# 1301_10A_01_400_1.net
KiCad netlist of a schematic drawn in Altium Designer
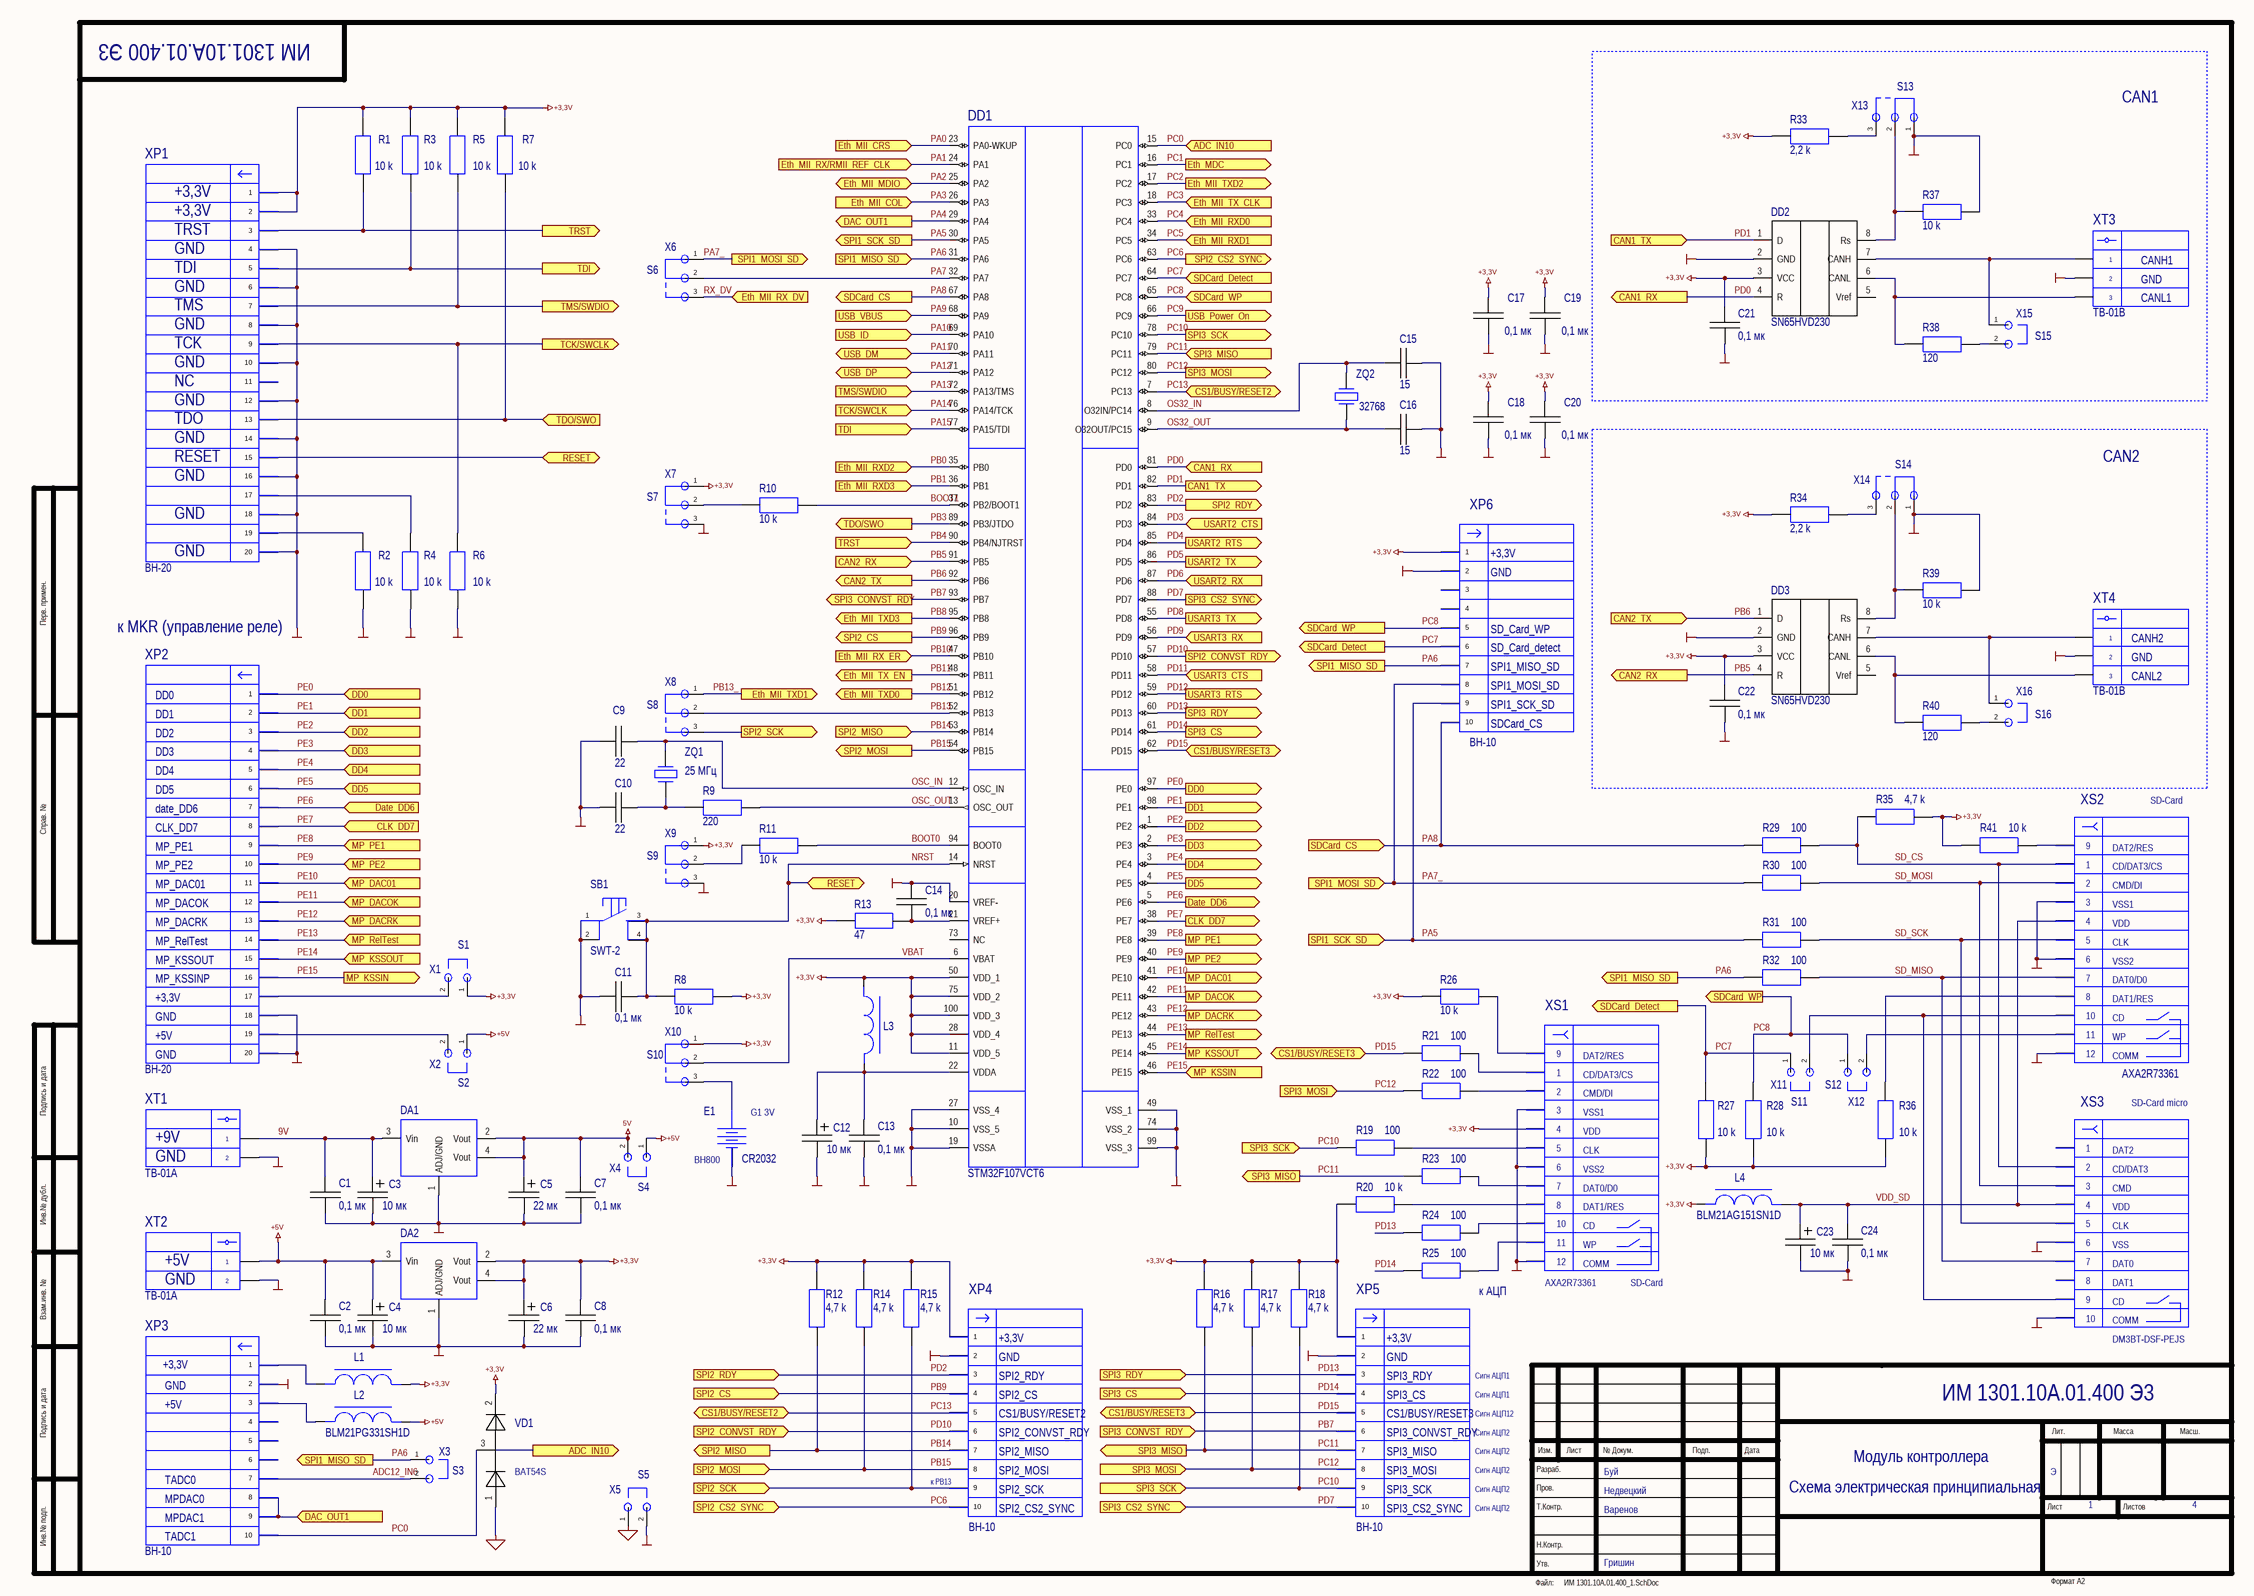
[diagram p0: ИМ 1301.10A.01.400_1.SchDoc]

(export (version "E")
  (design (tool "Eeschema 10.0.6"))
  (components
    (comp (ref "C1")
      (value "0,1 мк")
      (footprint "CAPC_1206")
      (description "Capasitor")
      (fields (field (name "PART NUMBER") "C"))
      (libsource (lib "RLC_GOST") (part "C"))
    )
    (comp (ref "C2")
      (value "0,1 мк")
      (footprint "CAPC_1206")
      (description "Capasitor")
      (fields (field (name "PART NUMBER") "C"))
      (libsource (lib "RLC_GOST") (part "C"))
    )
    (comp (ref "C3")
      (value "10 мк")
      (footprint "3216")
      (description "Capasitor_polar")
      (fields (field (name "PART NUMBER") "CapPol"))
      (libsource (lib "RLC_GOST") (part "CapPol"))
    )
    (comp (ref "C4")
      (value "10 мк")
      (footprint "3216")
      (description "Capasitor_polar")
      (fields (field (name "PART NUMBER") "CapPol"))
      (libsource (lib "RLC_GOST") (part "CapPol"))
    )
    (comp (ref "C5")
      (value "22 мк")
      (footprint "3216")
      (description "Capasitor_polar")
      (fields (field (name "PART NUMBER") "CapPol"))
      (libsource (lib "RLC_GOST") (part "CapPol"))
    )
    (comp (ref "C6")
      (value "22 мк")
      (footprint "3216")
      (description "Capasitor_polar")
      (fields (field (name "PART NUMBER") "CapPol"))
      (libsource (lib "RLC_GOST") (part "CapPol"))
    )
    (comp (ref "C7")
      (value "0,1 мк")
      (footprint "CAPC_1206")
      (description "Capasitor")
      (fields (field (name "PART NUMBER") "C"))
      (libsource (lib "RLC_GOST") (part "C"))
    )
    (comp (ref "C8")
      (value "0,1 мк")
      (footprint "CAPC_1206")
      (description "Capasitor")
      (fields (field (name "PART NUMBER") "C"))
      (libsource (lib "RLC_GOST") (part "C"))
    )
    (comp (ref "C9")
      (value "22")
      (footprint "CAPC_1206")
      (description "Capasitor")
      (libsource (lib "RLC_GOST") (part "C"))
    )
    (comp (ref "C10")
      (value "22")
      (footprint "CAPC_1206")
      (description "Capasitor")
      (libsource (lib "RLC_GOST") (part "C"))
    )
    (comp (ref "C11")
      (value "0,1 мк")
      (footprint "CAPC_1206")
      (description "Capasitor")
      (libsource (lib "RLC_GOST") (part "C"))
    )
    (comp (ref "C12")
      (value "10 мк")
      (footprint "3216")
      (description "Capasitor_polar")
      (fields (field (name "PART NUMBER") "CapPol"))
      (libsource (lib "RLC_GOST") (part "CapPol"))
    )
    (comp (ref "C13")
      (value "0,1 мк")
      (footprint "CAPC_1206")
      (description "Capasitor")
      (fields (field (name "PART NUMBER") "C"))
      (libsource (lib "RLC_GOST") (part "C"))
    )
    (comp (ref "C14")
      (value "0,1 мк")
      (footprint "CAPC_1206")
      (description "Capasitor")
      (fields (field (name "PART NUMBER") "C"))
      (libsource (lib "RLC_GOST") (part "C"))
    )
    (comp (ref "C15")
      (value "15")
      (footprint "CAPC_1206")
      (description "Capasitor")
      (libsource (lib "RLC_GOST") (part "C"))
    )
    (comp (ref "C16")
      (value "15")
      (footprint "CAPC_1206")
      (description "Capasitor")
      (libsource (lib "RLC_GOST") (part "C"))
    )
    (comp (ref "C17")
      (value "0,1 мк")
      (footprint "CAPC_1206")
      (description "Capasitor")
      (fields (field (name "PART NUMBER") "C"))
      (libsource (lib "RLC_GOST") (part "C"))
    )
    (comp (ref "C18")
      (value "0,1 мк")
      (footprint "CAPC_1206")
      (description "Capasitor")
      (fields (field (name "PART NUMBER") "C"))
      (libsource (lib "RLC_GOST") (part "C"))
    )
    (comp (ref "C19")
      (value "0,1 мк")
      (footprint "CAPC_1206")
      (description "Capasitor")
      (fields (field (name "PART NUMBER") "C"))
      (libsource (lib "RLC_GOST") (part "C"))
    )
    (comp (ref "C20")
      (value "0,1 мк")
      (footprint "CAPC_1206")
      (description "Capasitor")
      (fields (field (name "PART NUMBER") "C"))
      (libsource (lib "RLC_GOST") (part "C"))
    )
    (comp (ref "C21")
      (value "0,1 мк")
      (footprint "CAPC_1206")
      (description "Capasitor")
      (fields (field (name "PART NUMBER") "C"))
      (libsource (lib "RLC_GOST") (part "C"))
    )
    (comp (ref "C22")
      (value "0,1 мк")
      (footprint "CAPC_1206")
      (description "Capasitor")
      (fields (field (name "PART NUMBER") "C"))
      (libsource (lib "RLC_GOST") (part "C"))
    )
    (comp (ref "C23")
      (value "10 мк")
      (footprint "3216")
      (description "Capasitor_polar")
      (fields (field (name "PART NUMBER") "CapPol"))
      (libsource (lib "RLC_GOST") (part "CapPol"))
    )
    (comp (ref "C24")
      (value "0,1 мк")
      (footprint "CAPC_1206")
      (description "Capasitor")
      (fields (field (name "PART NUMBER") "C"))
      (libsource (lib "RLC_GOST") (part "C"))
    )
    (comp (ref "DA1")
      (value "LM1117")
      (footprint "SOT223")
      (description "Positive voltage regulators")
      (fields (field (name "MANUFACTURER") "National Semiconductor"))
      (libsource (lib "Stabil") (part "LM1117"))
    )
    (comp (ref "DA2")
      (value "LM1117")
      (footprint "SOT223")
      (description "Positive voltage regulators")
      (fields (field (name "MANUFACTURER") "National Semiconductor"))
      (libsource (lib "Stabil") (part "LM1117"))
    )
    (comp (ref "DD1")
      (value "STM32F107VCT6")
      (footprint "LQFP100")
      (description "STM32 ARM-based 32-bit MCU with 256 Kbytes Flash, 100-pin LQFP, Industrial Temperature")
      (fields (field (name "PUBLISHER") "Altium Limited"))
      (libsource (lib "STM32") (part "STM32F107VCT6"))
    )
    (comp (ref "DD2")
      (value "SN65HVD230")
      (footprint "SO8")
      (description "CAN transceivers")
      (libsource (lib "CAN") (part "SN65HVD230"))
    )
    (comp (ref "DD3")
      (value "SN65HVD230")
      (footprint "SO8")
      (description "CAN transceivers")
      (libsource (lib "CAN") (part "SN65HVD230"))
    )
    (comp (ref "E1")
      (value "BH800")
      (footprint "BATTERY_20mm")
      (fields (field (name "ALTIUM_VALUE") "CR2032") (field (name "G") "G1 3V"))
      (libsource (lib "Connectors") (part "BH800"))
    )
    (comp (ref "L1")
      (value "BLM21PG331SH1D")
      (footprint "C0805")
      (description "Ferrite bead")
      (libsource (lib "RLC_GOST") (part "B"))
    )
    (comp (ref "L2")
      (value "BLM21PG331SH1D")
      (footprint "C0805")
      (description "Ferrite bead")
      (libsource (lib "RLC_GOST") (part "B"))
    )
    (comp (ref "L3")
      (value "BLM21AG151SN1D")
      (footprint "C0805")
      (description "Ferrite bead")
      (libsource (lib "RLC_GOST") (part "B"))
    )
    (comp (ref "L4")
      (value "BLM21AG151SN1D")
      (footprint "C0805")
      (description "Ferrite bead")
      (libsource (lib "RLC_GOST") (part "B"))
    )
    (comp (ref "R1")
      (value "10 k")
      (footprint "SMD_1206")
      (description "Resistor,2 Pin")
      (libsource (lib "RLC_GOST") (part "R_Gost"))
    )
    (comp (ref "R2")
      (value "10 k")
      (footprint "SMD_1206")
      (description "Resistor,2 Pin")
      (libsource (lib "RLC_GOST") (part "R_Gost"))
    )
    (comp (ref "R3")
      (value "10 k")
      (footprint "SMD_1206")
      (description "Resistor,2 Pin")
      (libsource (lib "RLC_GOST") (part "R_Gost"))
    )
    (comp (ref "R4")
      (value "10 k")
      (footprint "SMD_1206")
      (description "Resistor,2 Pin")
      (libsource (lib "RLC_GOST") (part "R_Gost"))
    )
    (comp (ref "R5")
      (value "10 k")
      (footprint "SMD_1206")
      (description "Resistor,2 Pin")
      (libsource (lib "RLC_GOST") (part "R_Gost"))
    )
    (comp (ref "R6")
      (value "10 k")
      (footprint "SMD_1206")
      (description "Resistor,2 Pin")
      (libsource (lib "RLC_GOST") (part "R_Gost"))
    )
    (comp (ref "R7")
      (value "10 k")
      (footprint "SMD_1206")
      (description "Resistor,2 Pin")
      (libsource (lib "RLC_GOST") (part "R_Gost"))
    )
    (comp (ref "R8")
      (value "10 k")
      (footprint "SMD_1206")
      (description "Resistor,2 Pin")
      (libsource (lib "RLC_GOST") (part "R_Gost"))
    )
    (comp (ref "R9")
      (value "220")
      (footprint "SMD_1206")
      (description "Resistor,2 Pin")
      (libsource (lib "RLC_GOST") (part "R_Gost"))
    )
    (comp (ref "R10")
      (value "10 k")
      (footprint "SMD_1206")
      (description "Resistor,2 Pin")
      (libsource (lib "RLC_GOST") (part "R_Gost"))
    )
    (comp (ref "R11")
      (value "10 k")
      (footprint "SMD_1206")
      (description "Resistor,2 Pin")
      (libsource (lib "RLC_GOST") (part "R_Gost"))
    )
    (comp (ref "R12")
      (value "4,7 k")
      (footprint "SMD_1206")
      (description "Resistor,2 Pin")
      (libsource (lib "RLC_GOST") (part "R_Gost"))
    )
    (comp (ref "R13")
      (value "47")
      (footprint "SMD_1206")
      (description "Resistor,2 Pin")
      (libsource (lib "RLC_GOST") (part "R_Gost"))
    )
    (comp (ref "R14")
      (value "4,7 k")
      (footprint "SMD_1206")
      (description "Resistor,2 Pin")
      (libsource (lib "RLC_GOST") (part "R_Gost"))
    )
    (comp (ref "R15")
      (value "4,7 k")
      (footprint "SMD_1206")
      (description "Resistor,2 Pin")
      (libsource (lib "RLC_GOST") (part "R_Gost"))
    )
    (comp (ref "R16")
      (value "4,7 k")
      (footprint "SMD_1206")
      (description "Resistor,2 Pin")
      (libsource (lib "RLC_GOST") (part "R_Gost"))
    )
    (comp (ref "R17")
      (value "4,7 k")
      (footprint "SMD_1206")
      (description "Resistor,2 Pin")
      (libsource (lib "RLC_GOST") (part "R_Gost"))
    )
    (comp (ref "R18")
      (value "4,7 k")
      (footprint "SMD_1206")
      (description "Resistor,2 Pin")
      (libsource (lib "RLC_GOST") (part "R_Gost"))
    )
    (comp (ref "R19")
      (value "100")
      (footprint "SMD_1206")
      (description "Resistor,2 Pin")
      (libsource (lib "RLC_GOST") (part "R_Gost"))
    )
    (comp (ref "R20")
      (value "10 k")
      (footprint "SMD_1206")
      (description "Resistor,2 Pin")
      (libsource (lib "RLC_GOST") (part "R_Gost"))
    )
    (comp (ref "R21")
      (value "100")
      (footprint "SMD_1206")
      (description "Resistor,2 Pin")
      (libsource (lib "RLC_GOST") (part "R_Gost"))
    )
    (comp (ref "R22")
      (value "100")
      (footprint "SMD_1206")
      (description "Resistor,2 Pin")
      (libsource (lib "RLC_GOST") (part "R_Gost"))
    )
    (comp (ref "R23")
      (value "100")
      (footprint "SMD_1206")
      (description "Resistor,2 Pin")
      (libsource (lib "RLC_GOST") (part "R_Gost"))
    )
    (comp (ref "R24")
      (value "100")
      (footprint "SMD_1206")
      (description "Resistor,2 Pin")
      (libsource (lib "RLC_GOST") (part "R_Gost"))
    )
    (comp (ref "R25")
      (value "100")
      (footprint "SMD_1206")
      (description "Resistor,2 Pin")
      (libsource (lib "RLC_GOST") (part "R_Gost"))
    )
    (comp (ref "R26")
      (value "10 k")
      (footprint "SMD_1206")
      (description "Resistor,2 Pin")
      (libsource (lib "RLC_GOST") (part "R_Gost"))
    )
    (comp (ref "R27")
      (value "10 k")
      (footprint "SMD_1206")
      (description "Resistor,2 Pin")
      (libsource (lib "RLC_GOST") (part "R_Gost"))
    )
    (comp (ref "R28")
      (value "10 k")
      (footprint "SMD_1206")
      (description "Resistor,2 Pin")
      (libsource (lib "RLC_GOST") (part "R_Gost"))
    )
    (comp (ref "R29")
      (value "100")
      (footprint "SMD_1206")
      (description "Resistor,2 Pin")
      (libsource (lib "RLC_GOST") (part "R_Gost"))
    )
    (comp (ref "R30")
      (value "100")
      (footprint "SMD_1206")
      (description "Resistor,2 Pin")
      (libsource (lib "RLC_GOST") (part "R_Gost"))
    )
    (comp (ref "R31")
      (value "100")
      (footprint "SMD_1206")
      (description "Resistor,2 Pin")
      (libsource (lib "RLC_GOST") (part "R_Gost"))
    )
    (comp (ref "R32")
      (value "100")
      (footprint "SMD_1206")
      (description "Resistor,2 Pin")
      (libsource (lib "RLC_GOST") (part "R_Gost"))
    )
    (comp (ref "R33")
      (value "2,2 k")
      (footprint "SMD_1206")
      (description "Resistor,2 Pin")
      (libsource (lib "RLC_GOST") (part "R_Gost"))
    )
    (comp (ref "R34")
      (value "2,2 k")
      (footprint "SMD_1206")
      (description "Resistor,2 Pin")
      (libsource (lib "RLC_GOST") (part "R_Gost"))
    )
    (comp (ref "R35")
      (value "4,7 k")
      (footprint "SMD_1206")
      (description "Resistor,2 Pin")
      (libsource (lib "RLC_GOST") (part "R_Gost"))
    )
    (comp (ref "R36")
      (value "10 k")
      (footprint "SMD_1206")
      (description "Resistor,2 Pin")
      (libsource (lib "RLC_GOST") (part "R_Gost"))
    )
    (comp (ref "R37")
      (value "10 k")
      (footprint "SMD_1206")
      (description "Resistor,2 Pin")
      (libsource (lib "RLC_GOST") (part "R_Gost"))
    )
    (comp (ref "R38")
      (value "120")
      (footprint "SMD_1206")
      (description "Resistor,2 Pin")
      (libsource (lib "RLC_GOST") (part "R_Gost"))
    )
    (comp (ref "R39")
      (value "10 k")
      (footprint "SMD_1206")
      (description "Resistor,2 Pin")
      (libsource (lib "RLC_GOST") (part "R_Gost"))
    )
    (comp (ref "R40")
      (value "120")
      (footprint "SMD_1206")
      (description "Resistor,2 Pin")
      (libsource (lib "RLC_GOST") (part "R_Gost"))
    )
    (comp (ref "R41")
      (value "10 k")
      (footprint "SMD_1206")
      (description "Resistor,2 Pin")
      (libsource (lib "RLC_GOST") (part "R_Gost"))
    )
    (comp (ref "SB1")
      (value "SWT-2")
      (footprint "SWT2")
      (description "SWT-2, key")
      (libsource (lib "Keys") (part "SWT-2"))
    )
    (comp (ref "VD1")
      (value "BAT54S")
      (footprint "SOT23")
      (description "Diod Schottky, 3 pin")
      (fields (field (name "MANUFACTURER") "Fairchild"))
      (libsource (lib "Diod") (part "BS40-04"))
    )
    (comp (ref "X1")
      (value "PLS-02")
      (footprint "PLS-2")
      (fields (field (name "JAMPER") "S1"))
      (libsource (lib "Connectors") (part "J2"))
    )
    (comp (ref "X2")
      (value "PLS-02")
      (footprint "PLS-2")
      (fields (field (name "JAMPER") "S2"))
      (libsource (lib "Connectors") (part "J2"))
    )
    (comp (ref "X3")
      (value "PLS-02")
      (footprint "PLS-2")
      (fields (field (name "JAMPER") "S3"))
      (libsource (lib "Connectors") (part "J2"))
    )
    (comp (ref "X4")
      (value "PLS-02")
      (footprint "PLS-2")
      (fields (field (name "JAMPER") "S4"))
      (libsource (lib "Connectors") (part "J2"))
    )
    (comp (ref "X5")
      (value "PLS-02")
      (footprint "PLS-2")
      (fields (field (name "JAMPER") "S5"))
      (libsource (lib "Connectors") (part "J2"))
    )
    (comp (ref "X6")
      (value "PLS-03")
      (footprint "PLS-3")
      (fields (field (name "JAMPER") "S6"))
      (libsource (lib "Connectors") (part "J3"))
    )
    (comp (ref "X7")
      (value "PLS-03")
      (footprint "PLS-3")
      (fields (field (name "JAMPER") "S7"))
      (libsource (lib "Connectors") (part "J3"))
    )
    (comp (ref "X8")
      (value "PLS-03")
      (footprint "PLS-3")
      (fields (field (name "JAMPER") "S8"))
      (libsource (lib "Connectors") (part "J3"))
    )
    (comp (ref "X9")
      (value "PLS-03")
      (footprint "PLS-3")
      (fields (field (name "JAMPER") "S9"))
      (libsource (lib "Connectors") (part "J3"))
    )
    (comp (ref "X10")
      (value "PLS-03")
      (footprint "PLS-3")
      (fields (field (name "JAMPER") "S10"))
      (libsource (lib "Connectors") (part "J3"))
    )
    (comp (ref "X11")
      (value "PLS-02")
      (footprint "PLS-2")
      (fields (field (name "JAMPER") "S11"))
      (libsource (lib "Connectors") (part "J2"))
    )
    (comp (ref "X12")
      (value "PLS-02")
      (footprint "PLS-2")
      (fields (field (name "JAMPER") "S12"))
      (libsource (lib "Connectors") (part "J2"))
    )
    (comp (ref "X13")
      (value "PLS-03")
      (footprint "PLS-3")
      (fields (field (name "JAMPER") "S13"))
      (libsource (lib "Connectors") (part "J3"))
    )
    (comp (ref "X14")
      (value "PLS-03")
      (footprint "PLS-3")
      (fields (field (name "JAMPER") "S14"))
      (libsource (lib "Connectors") (part "J3"))
    )
    (comp (ref "X15")
      (value "PLS-02")
      (footprint "PLS-2")
      (fields (field (name "JAMPER") "S15"))
      (libsource (lib "Connectors") (part "J2"))
    )
    (comp (ref "X16")
      (value "PLS-02")
      (footprint "PLS-2")
      (fields (field (name "JAMPER") "S16"))
      (libsource (lib "Connectors") (part "J2"))
    )
    (comp (ref "XP1") (value "BH-20") (footprint "PLD-20") (libsource (lib "Connectors") (part "BH-20")))
    (comp (ref "XP2") (value "BH-20") (footprint "PLD-20") (libsource (lib "Connectors") (part "BH-20")))
    (comp (ref "XP3") (value "BH-10") (footprint "PLD-10") (libsource (lib "Connectors") (part "BH-10")))
    (comp (ref "XP4") (value "BH-10") (footprint "PLD-10") (libsource (lib "Connectors") (part "BH-10")))
    (comp (ref "XP5") (value "BH-10") (footprint "PLD-10") (libsource (lib "Connectors") (part "BH-10")))
    (comp (ref "XP6") (value "BH-10") (footprint "PLD-10") (libsource (lib "Connectors") (part "BH-10")))
    (comp (ref "XS1")
      (value "AXA2R73361")
      (footprint "SD_AXA2R")
      (description "SD-card socket")
      (fields (field (name "FUNCTION") "SD-Card"))
      (libsource (lib "Connectors") (part "SDcard"))
    )
    (comp (ref "XS2")
      (value "AXA2R73361")
      (footprint "SD_AXA2R")
      (description "SD-card socket")
      (fields (field (name "FUNCTION") "SD-Card"))
      (libsource (lib "Connectors") (part "SDcard"))
    )
    (comp (ref "XS3")
      (value "DM3BT-DSF-PEJS")
      (footprint "DM3BT-DSF-PEJS")
      (description "SD-card socket")
      (fields (field (name "FUNCTION") "SD-Card micro"))
      (libsource (lib "Connectors") (part "MicroSD"))
    )
    (comp (ref "XT1") (value "TB-01A") (footprint "TB-01A") (libsource (lib "Connectors") (part "TB-01A")))
    (comp (ref "XT2") (value "TB-01A") (footprint "TB-01A") (libsource (lib "Connectors") (part "TB-01A")))
    (comp (ref "XT3") (value "TB-01B") (footprint "TB-01B") (libsource (lib "Connectors") (part "TB-01B")))
    (comp (ref "XT4") (value "TB-01B") (footprint "TB-01B") (libsource (lib "Connectors") (part "TB-01B")))
    (comp (ref "ZQ1")
      (value "25 МГц")
      (footprint "HC-49U_5mm")
      (description "OSC")
      (libsource (lib "Resonators") (part "OSC"))
    )
    (comp (ref "ZQ2")
      (value "32768")
      (footprint "DT-38P")
      (description "OSC")
      (libsource (lib "Resonators") (part "OSC"))
    )
  )
  (nets
    (net (code "1") (name "+3,3V") (class "Default")
      (node (ref "C17") (pin "1") (pinfunction "1_1") (pintype "passive"))
      (node (ref "C18") (pin "1") (pinfunction "1_1") (pintype "passive"))
      (node (ref "C19") (pin "1") (pinfunction "1_1") (pintype "passive"))
      (node (ref "C20") (pin "1") (pinfunction "1_1") (pintype "passive"))
      (node (ref "C21") (pin "1") (pinfunction "1_1") (pintype "passive"))
      (node (ref "C22") (pin "1") (pinfunction "1_1") (pintype "passive"))
      (node (ref "C6") (pin "1") (pinfunction "+_1") (pintype "passive"))
      (node (ref "C8") (pin "1") (pinfunction "1_1") (pintype "passive"))
      (node (ref "DA2") (pin "2") (pinfunction "Vout_2") (pintype "power_in"))
      (node (ref "DA2") (pin "4") (pinfunction "Vout_4") (pintype "passive"))
      (node (ref "DD1") (pin "100") (pinfunction "VDD_3_100") (pintype "power_in"))
      (node (ref "DD1") (pin "11") (pinfunction "VDD_5_11") (pintype "power_in"))
      (node (ref "DD1") (pin "28") (pinfunction "VDD_4_28") (pintype "power_in"))
      (node (ref "DD1") (pin "50") (pinfunction "VDD_1_50") (pintype "power_in"))
      (node (ref "DD1") (pin "75") (pinfunction "VDD_2_75") (pintype "power_in"))
      (node (ref "DD2") (pin "3") (pinfunction "VCC_3") (pintype "power_in"))
      (node (ref "DD3") (pin "3") (pinfunction "VCC_3") (pintype "power_in"))
      (node (ref "L1") (pin "2") (pinfunction "2_2") (pintype "passive"))
      (node (ref "L3") (pin "1") (pinfunction "1_1") (pintype "passive"))
      (node (ref "L4") (pin "1") (pinfunction "1_1") (pintype "passive"))
      (node (ref "R1") (pin "2") (pinfunction "2_2") (pintype "passive"))
      (node (ref "R12") (pin "2") (pinfunction "2_2") (pintype "passive"))
      (node (ref "R13") (pin "2") (pinfunction "2_2") (pintype "passive"))
      (node (ref "R14") (pin "2") (pinfunction "2_2") (pintype "passive"))
      (node (ref "R15") (pin "2") (pinfunction "2_2") (pintype "passive"))
      (node (ref "R16") (pin "2") (pinfunction "2_2") (pintype "passive"))
      (node (ref "R17") (pin "2") (pinfunction "2_2") (pintype "passive"))
      (node (ref "R18") (pin "2") (pinfunction "2_2") (pintype "passive"))
      (node (ref "R20") (pin "2") (pinfunction "2_2") (pintype "passive"))
      (node (ref "R26") (pin "1") (pinfunction "1_1") (pintype "passive"))
      (node (ref "R27") (pin "2") (pinfunction "2_2") (pintype "passive"))
      (node (ref "R28") (pin "2") (pinfunction "2_2") (pintype "passive"))
      (node (ref "R3") (pin "2") (pinfunction "2_2") (pintype "passive"))
      (node (ref "R33") (pin "1") (pinfunction "1_1") (pintype "passive"))
      (node (ref "R34") (pin "1") (pinfunction "1_1") (pintype "passive"))
      (node (ref "R35") (pin "1") (pinfunction "1_1") (pintype "passive"))
      (node (ref "R36") (pin "2") (pinfunction "2_2") (pintype "passive"))
      (node (ref "R41") (pin "2") (pinfunction "2_2") (pintype "passive"))
      (node (ref "R5") (pin "2") (pinfunction "2_2") (pintype "passive"))
      (node (ref "R7") (pin "2") (pinfunction "2_2") (pintype "passive"))
      (node (ref "R8") (pin "2") (pinfunction "2_2") (pintype "passive"))
      (node (ref "VD1") (pin "2") (pinfunction "-_2") (pintype "passive"))
      (node (ref "X1") (pin "1") (pinfunction "1_1") (pintype "passive"))
      (node (ref "X10") (pin "1") (pinfunction "1_1") (pintype "passive"))
      (node (ref "X7") (pin "1") (pinfunction "1_1") (pintype "passive"))
      (node (ref "X9") (pin "1") (pinfunction "1_1") (pintype "passive"))
      (node (ref "XP1") (pin "1") (pinfunction "1_1") (pintype "passive"))
      (node (ref "XP1") (pin "2") (pinfunction "2_2") (pintype "passive"))
      (node (ref "XP4") (pin "1") (pinfunction "1_1") (pintype "passive"))
      (node (ref "XP5") (pin "1") (pinfunction "1_1") (pintype "passive"))
      (node (ref "XP6") (pin "1") (pinfunction "1_1") (pintype "passive"))
      (node (ref "XS1") (pin "4") (pinfunction "4_4") (pintype "passive"))
    )
    (net (code "2") (name "+5V") (class "Default")
      (node (ref "C2") (pin "1") (pinfunction "1_1") (pintype "passive"))
      (node (ref "C4") (pin "1") (pinfunction "+_1") (pintype "passive"))
      (node (ref "DA2") (pin "3") (pinfunction "Vin_3") (pintype "power_in"))
      (node (ref "L2") (pin "2") (pinfunction "2_2") (pintype "passive"))
      (node (ref "X2") (pin "1") (pinfunction "1_1") (pintype "passive"))
      (node (ref "X4") (pin "1") (pinfunction "1_1") (pintype "passive"))
      (node (ref "XT2") (pin "1") (pintype "passive"))
    )
    (net (code "3") (name "/9V") (class "Default")
      (node (ref "C1") (pin "1") (pinfunction "1_1") (pintype "passive"))
      (node (ref "C3") (pin "1") (pinfunction "+_1") (pintype "passive"))
      (node (ref "DA1") (pin "3") (pinfunction "Vin_3") (pintype "power_in"))
      (node (ref "XT1") (pin "1") (pintype "passive"))
    )
    (net (code "4") (name "/ADC12_IN6") (class "Default")
      (node (ref "X3") (pin "2") (pinfunction "2_2") (pintype "passive"))
      (node (ref "XP3") (pin "7") (pinfunction "7_7") (pintype "passive"))
    )
    (net (code "5") (name "/BOOT0") (class "Default")
      (node (ref "DD1") (pin "94") (pinfunction "BOOT0_94") (pintype "passive"))
      (node (ref "R11") (pin "2") (pinfunction "2_2") (pintype "passive"))
    )
    (net (code "6") (name "/BOOT1") (class "Default")
      (node (ref "DD1") (pin "37") (pinfunction "PB2/BOOT1_37") (pintype "bidirectional"))
      (node (ref "R10") (pin "2") (pinfunction "2_2") (pintype "passive"))
    )
    (net (code "7") (name "/NRST") (class "Default")
      (node (ref "C11") (pin "2") (pinfunction "2_2") (pintype "passive"))
      (node (ref "DD1") (pin "14") (pinfunction "NRST_14") (pintype "input"))
      (node (ref "R8") (pin "1") (pinfunction "1_1") (pintype "passive"))
      (node (ref "SB1") (pin "3") (pinfunction "3_3") (pintype "passive"))
      (node (ref "SB1") (pin "4") (pinfunction "4_4") (pintype "passive"))
      (node (ref "XP1") (pin "15") (pinfunction "15_15") (pintype "passive"))
    )
    (net (code "8") (name "/OS32_IN") (class "Default")
      (node (ref "C15") (pin "1") (pinfunction "1_1") (pintype "passive"))
      (node (ref "DD1") (pin "8") (pinfunction "O32IN/PC14_8") (pintype "bidirectional"))
      (node (ref "ZQ2") (pin "1") (pinfunction "1_1") (pintype "passive"))
    )
    (net (code "9") (name "/OS32_OUT") (class "Default")
      (node (ref "C16") (pin "1") (pinfunction "1_1") (pintype "passive"))
      (node (ref "DD1") (pin "9") (pinfunction "O32OUT/PC15_9") (pintype "bidirectional"))
      (node (ref "ZQ2") (pin "2") (pinfunction "2_2") (pintype "passive"))
    )
    (net (code "10") (name "/OSC_IN") (class "Default")
      (node (ref "C9") (pin "2") (pinfunction "2_2") (pintype "passive"))
      (node (ref "DD1") (pin "12") (pinfunction "OSC_IN_12") (pintype "input"))
      (node (ref "ZQ1") (pin "2") (pinfunction "2_2") (pintype "passive"))
    )
    (net (code "11") (name "/OSC_OUT") (class "Default")
      (node (ref "DD1") (pin "13") (pinfunction "OSC_OUT_13") (pintype "output"))
      (node (ref "R9") (pin "2") (pinfunction "2_2") (pintype "passive"))
    )
    (net (code "12") (name "/PA0") (class "Default")
      (node (ref "DD1") (pin "23") (pinfunction "PA0-WKUP_23") (pintype "bidirectional"))
    )
    (net (code "13") (name "/PA1") (class "Default")
      (node (ref "DD1") (pin "24") (pinfunction "PA1_24") (pintype "bidirectional"))
    )
    (net (code "14") (name "/PA2") (class "Default")
      (node (ref "DD1") (pin "25") (pinfunction "PA2_25") (pintype "bidirectional"))
    )
    (net (code "15") (name "/PA3") (class "Default")
      (node (ref "DD1") (pin "26") (pinfunction "PA3_26") (pintype "bidirectional"))
    )
    (net (code "16") (name "/PA4") (class "Default")
      (node (ref "DD1") (pin "29") (pinfunction "PA4_29") (pintype "bidirectional"))
      (node (ref "XP3") (pin "8") (pinfunction "8_8") (pintype "passive"))
      (node (ref "XP3") (pin "9") (pinfunction "9_9") (pintype "passive"))
    )
    (net (code "17") (name "/PA5") (class "Default")
      (node (ref "DD1") (pin "30") (pinfunction "PA5_30") (pintype "bidirectional"))
      (node (ref "R31") (pin "2") (pinfunction "2_2") (pintype "passive"))
      (node (ref "XP6") (pin "9") (pinfunction "9_9") (pintype "passive"))
    )
    (net (code "18") (name "/PA6") (class "Default")
      (node (ref "DD1") (pin "31") (pinfunction "PA6_31") (pintype "bidirectional"))
      (node (ref "R32") (pin "2") (pinfunction "2_2") (pintype "passive"))
      (node (ref "X3") (pin "1") (pinfunction "1_1") (pintype "passive"))
      (node (ref "XP6") (pin "7") (pinfunction "7_7") (pintype "passive"))
    )
    (net (code "19") (name "/PA7") (class "Default")
      (node (ref "DD1") (pin "32") (pinfunction "PA7_32") (pintype "bidirectional"))
      (node (ref "X6") (pin "2") (pinfunction "2_2") (pintype "passive"))
    )
    (net (code "20") (name "/PA7_") (class "Default")
      (node (ref "R30") (pin "2") (pinfunction "2_2") (pintype "passive"))
      (node (ref "X6") (pin "1") (pinfunction "1_1") (pintype "passive"))
      (node (ref "XP6") (pin "8") (pinfunction "8_8") (pintype "passive"))
    )
    (net (code "21") (name "/PA8") (class "Default")
      (node (ref "DD1") (pin "67") (pinfunction "PA8_67") (pintype "bidirectional"))
      (node (ref "R29") (pin "2") (pinfunction "2_2") (pintype "passive"))
      (node (ref "XP6") (pin "10") (pinfunction "10_10") (pintype "passive"))
    )
    (net (code "22") (name "/PA9") (class "Default")
      (node (ref "DD1") (pin "68") (pinfunction "PA9_68") (pintype "bidirectional"))
    )
    (net (code "23") (name "/PA10") (class "Default")
      (node (ref "DD1") (pin "69") (pinfunction "PA10_69") (pintype "bidirectional"))
    )
    (net (code "24") (name "/PA11") (class "Default")
      (node (ref "DD1") (pin "70") (pinfunction "PA11_70") (pintype "bidirectional"))
    )
    (net (code "25") (name "/PA12") (class "Default")
      (node (ref "DD1") (pin "71") (pinfunction "PA12_71") (pintype "bidirectional"))
    )
    (net (code "26") (name "/PA13") (class "Default")
      (node (ref "DD1") (pin "72") (pinfunction "PA13/TMS_72") (pintype "bidirectional"))
      (node (ref "R5") (pin "1") (pinfunction "1_1") (pintype "passive"))
      (node (ref "XP1") (pin "7") (pinfunction "7_7") (pintype "passive"))
    )
    (net (code "27") (name "/PA14") (class "Default")
      (node (ref "DD1") (pin "76") (pinfunction "PA14/TCK_76") (pintype "bidirectional"))
      (node (ref "R6") (pin "2") (pinfunction "2_2") (pintype "passive"))
      (node (ref "XP1") (pin "9") (pinfunction "9_9") (pintype "passive"))
    )
    (net (code "28") (name "/PA15") (class "Default")
      (node (ref "DD1") (pin "77") (pinfunction "PA15/TDI_77") (pintype "bidirectional"))
      (node (ref "R3") (pin "1") (pinfunction "1_1") (pintype "passive"))
      (node (ref "XP1") (pin "5") (pinfunction "5_5") (pintype "passive"))
    )
    (net (code "29") (name "/PB0") (class "Default")
      (node (ref "DD1") (pin "35") (pinfunction "PB0_35") (pintype "bidirectional"))
    )
    (net (code "30") (name "/PB1") (class "Default")
      (node (ref "DD1") (pin "36") (pinfunction "PB1_36") (pintype "bidirectional"))
    )
    (net (code "31") (name "/PB3") (class "Default")
      (node (ref "DD1") (pin "89") (pinfunction "PB3/JTDO_89") (pintype "bidirectional"))
      (node (ref "R7") (pin "1") (pinfunction "1_1") (pintype "passive"))
      (node (ref "XP1") (pin "13") (pinfunction "13_13") (pintype "passive"))
    )
    (net (code "32") (name "/PB4") (class "Default")
      (node (ref "DD1") (pin "90") (pinfunction "PB4/NJTRST_90") (pintype "bidirectional"))
      (node (ref "R1") (pin "1") (pinfunction "1_1") (pintype "passive"))
      (node (ref "XP1") (pin "3") (pinfunction "3_3") (pintype "passive"))
    )
    (net (code "33") (name "/PB5") (class "Default")
      (node (ref "DD1") (pin "91") (pinfunction "PB5_91") (pintype "bidirectional"))
      (node (ref "DD3") (pin "4") (pinfunction "R_4") (pintype "passive"))
    )
    (net (code "34") (name "/PB6") (class "Default")
      (node (ref "DD1") (pin "92") (pinfunction "PB6_92") (pintype "bidirectional"))
      (node (ref "DD3") (pin "1") (pinfunction "D_1") (pintype "passive"))
    )
    (net (code "35") (name "/PB7") (class "Default")
      (node (ref "DD1") (pin "93") (pinfunction "PB7_93") (pintype "bidirectional"))
      (node (ref "XP5") (pin "6") (pinfunction "6_6") (pintype "passive"))
    )
    (net (code "36") (name "/PB8") (class "Default")
      (node (ref "DD1") (pin "95") (pinfunction "PB8_95") (pintype "bidirectional"))
    )
    (net (code "37") (name "/PB9") (class "Default")
      (node (ref "DD1") (pin "96") (pinfunction "PB9_96") (pintype "bidirectional"))
      (node (ref "XP4") (pin "4") (pinfunction "4_4") (pintype "passive"))
    )
    (net (code "38") (name "/PB10") (class "Default")
      (node (ref "DD1") (pin "47") (pinfunction "PB10_47") (pintype "bidirectional"))
    )
    (net (code "39") (name "/PB11") (class "Default")
      (node (ref "DD1") (pin "48") (pinfunction "PB11_48") (pintype "bidirectional"))
    )
    (net (code "40") (name "/PB12") (class "Default")
      (node (ref "DD1") (pin "51") (pinfunction "PB12_51") (pintype "bidirectional"))
    )
    (net (code "41") (name "/PB13") (class "Default")
      (node (ref "DD1") (pin "52") (pinfunction "PB13_52") (pintype "bidirectional"))
      (node (ref "X8") (pin "2") (pinfunction "2_2") (pintype "passive"))
    )
    (net (code "42") (name "/PB13_") (class "Default")
      (node (ref "X8") (pin "1") (pinfunction "1_1") (pintype "passive"))
    )
    (net (code "43") (name "/PB14") (class "Default")
      (node (ref "DD1") (pin "53") (pinfunction "PB14_53") (pintype "bidirectional"))
      (node (ref "R12") (pin "1") (pinfunction "1_1") (pintype "passive"))
      (node (ref "XP4") (pin "7") (pinfunction "7_7") (pintype "passive"))
    )
    (net (code "44") (name "/PB15") (class "Default")
      (node (ref "DD1") (pin "54") (pinfunction "PB15_54") (pintype "bidirectional"))
      (node (ref "R14") (pin "1") (pinfunction "1_1") (pintype "passive"))
      (node (ref "XP4") (pin "8") (pinfunction "8_8") (pintype "passive"))
    )
    (net (code "45") (name "/PC0") (class "Default")
      (node (ref "DD1") (pin "15") (pinfunction "PC0_15") (pintype "bidirectional"))
      (node (ref "VD1") (pin "3") (pintype "passive"))
      (node (ref "XP3") (pin "10") (pinfunction "10_10") (pintype "passive"))
    )
    (net (code "46") (name "/PC1") (class "Default")
      (node (ref "DD1") (pin "16") (pinfunction "PC1_16") (pintype "bidirectional"))
    )
    (net (code "47") (name "/PC2") (class "Default")
      (node (ref "DD1") (pin "17") (pinfunction "PC2_17") (pintype "bidirectional"))
    )
    (net (code "48") (name "/PC3") (class "Default")
      (node (ref "DD1") (pin "18") (pinfunction "PC3_18") (pintype "bidirectional"))
    )
    (net (code "49") (name "/PC4") (class "Default")
      (node (ref "DD1") (pin "33") (pinfunction "PC4_33") (pintype "bidirectional"))
    )
    (net (code "50") (name "/PC5") (class "Default")
      (node (ref "DD1") (pin "34") (pinfunction "PC5_34") (pintype "bidirectional"))
    )
    (net (code "51") (name "/PC6") (class "Default")
      (node (ref "DD1") (pin "63") (pinfunction "PC6_63") (pintype "bidirectional"))
      (node (ref "XP4") (pin "10") (pinfunction "10_10") (pintype "passive"))
    )
    (net (code "52") (name "/PC7") (class "Default")
      (node (ref "DD1") (pin "64") (pinfunction "PC7_64") (pintype "bidirectional"))
      (node (ref "R27") (pin "1") (pinfunction "1_1") (pintype "passive"))
      (node (ref "X11") (pin "1") (pinfunction "1_1") (pintype "passive"))
      (node (ref "XP6") (pin "6") (pinfunction "6_6") (pintype "passive"))
    )
    (net (code "53") (name "/PC8") (class "Default")
      (node (ref "DD1") (pin "65") (pinfunction "PC8_65") (pintype "bidirectional"))
      (node (ref "R28") (pin "1") (pinfunction "1_1") (pintype "passive"))
      (node (ref "X12") (pin "1") (pinfunction "1_1") (pintype "passive"))
      (node (ref "XP6") (pin "5") (pinfunction "5_5") (pintype "passive"))
    )
    (net (code "54") (name "/PC9") (class "Default")
      (node (ref "DD1") (pin "66") (pinfunction "PC9_66") (pintype "bidirectional"))
    )
    (net (code "55") (name "/PC10") (class "Default")
      (node (ref "DD1") (pin "78") (pinfunction "PC10_78") (pintype "bidirectional"))
      (node (ref "R18") (pin "1") (pinfunction "1_1") (pintype "passive"))
      (node (ref "R19") (pin "2") (pinfunction "2_2") (pintype "passive"))
      (node (ref "XP5") (pin "9") (pinfunction "9_9") (pintype "passive"))
    )
    (net (code "56") (name "/PC11") (class "Default")
      (node (ref "DD1") (pin "79") (pinfunction "PC11_79") (pintype "bidirectional"))
      (node (ref "R16") (pin "1") (pinfunction "1_1") (pintype "passive"))
      (node (ref "R23") (pin "2") (pinfunction "2_2") (pintype "passive"))
      (node (ref "XP5") (pin "7") (pinfunction "7_7") (pintype "passive"))
    )
    (net (code "57") (name "/PC12") (class "Default")
      (node (ref "DD1") (pin "80") (pinfunction "PC12_80") (pintype "bidirectional"))
      (node (ref "R17") (pin "1") (pinfunction "1_1") (pintype "passive"))
      (node (ref "R22") (pin "2") (pinfunction "2_2") (pintype "passive"))
      (node (ref "XP5") (pin "8") (pinfunction "8_8") (pintype "passive"))
    )
    (net (code "58") (name "/PC13") (class "Default")
      (node (ref "DD1") (pin "7") (pinfunction "PC13_7") (pintype "bidirectional"))
      (node (ref "XP4") (pin "5") (pinfunction "5_5") (pintype "passive"))
    )
    (net (code "59") (name "/PD0") (class "Default")
      (node (ref "DD1") (pin "81") (pinfunction "PD0_81") (pintype "bidirectional"))
      (node (ref "DD2") (pin "4") (pinfunction "R_4") (pintype "passive"))
    )
    (net (code "60") (name "/PD1") (class "Default")
      (node (ref "DD1") (pin "82") (pinfunction "PD1_82") (pintype "bidirectional"))
      (node (ref "DD2") (pin "1") (pinfunction "D_1") (pintype "passive"))
    )
    (net (code "61") (name "/PD2") (class "Default")
      (node (ref "DD1") (pin "83") (pinfunction "PD2_83") (pintype "bidirectional"))
      (node (ref "XP4") (pin "3") (pinfunction "3_3") (pintype "passive"))
    )
    (net (code "62") (name "/PD3") (class "Default")
      (node (ref "DD1") (pin "84") (pinfunction "PD3_84") (pintype "bidirectional"))
    )
    (net (code "63") (name "/PD4") (class "Default")
      (node (ref "DD1") (pin "85") (pinfunction "PD4_85") (pintype "bidirectional"))
    )
    (net (code "64") (name "/PD5") (class "Default")
      (node (ref "DD1") (pin "86") (pinfunction "PD5_86") (pintype "bidirectional"))
    )
    (net (code "65") (name "/PD6") (class "Default")
      (node (ref "DD1") (pin "87") (pinfunction "PD6_87") (pintype "bidirectional"))
    )
    (net (code "66") (name "/PD7") (class "Default")
      (node (ref "DD1") (pin "88") (pinfunction "PD7_88") (pintype "bidirectional"))
      (node (ref "XP5") (pin "10") (pinfunction "10_10") (pintype "passive"))
    )
    (net (code "67") (name "/PD8") (class "Default")
      (node (ref "DD1") (pin "55") (pinfunction "PD8_55") (pintype "bidirectional"))
    )
    (net (code "68") (name "/PD9") (class "Default")
      (node (ref "DD1") (pin "56") (pinfunction "PD9_56") (pintype "bidirectional"))
    )
    (net (code "69") (name "/PD10") (class "Default")
      (node (ref "DD1") (pin "57") (pinfunction "PD10_57") (pintype "bidirectional"))
      (node (ref "XP4") (pin "6") (pinfunction "6_6") (pintype "passive"))
    )
    (net (code "70") (name "/PD11") (class "Default")
      (node (ref "DD1") (pin "58") (pinfunction "PD11_58") (pintype "bidirectional"))
    )
    (net (code "71") (name "/PD12") (class "Default")
      (node (ref "DD1") (pin "59") (pinfunction "PD12_59") (pintype "bidirectional"))
    )
    (net (code "72") (name "/PD13") (class "Default")
      (node (ref "DD1") (pin "60") (pinfunction "PD13_60") (pintype "bidirectional"))
      (node (ref "R24") (pin "2") (pinfunction "2_2") (pintype "passive"))
      (node (ref "XP5") (pin "3") (pinfunction "3_3") (pintype "passive"))
    )
    (net (code "73") (name "/PD14") (class "Default")
      (node (ref "DD1") (pin "61") (pinfunction "PD14_61") (pintype "bidirectional"))
      (node (ref "R25") (pin "2") (pinfunction "2_2") (pintype "passive"))
      (node (ref "XP5") (pin "4") (pinfunction "4_4") (pintype "passive"))
    )
    (net (code "74") (name "/PD15") (class "Default")
      (node (ref "DD1") (pin "62") (pinfunction "PD15_62") (pintype "bidirectional"))
      (node (ref "R21") (pin "2") (pinfunction "2_2") (pintype "passive"))
      (node (ref "XP5") (pin "5") (pinfunction "5_5") (pintype "passive"))
    )
    (net (code "75") (name "/PE0") (class "Default")
      (node (ref "DD1") (pin "97") (pinfunction "PE0_97") (pintype "bidirectional"))
      (node (ref "XP2") (pin "1") (pinfunction "1_1") (pintype "passive"))
    )
    (net (code "76") (name "/PE1") (class "Default")
      (node (ref "DD1") (pin "98") (pinfunction "PE1_98") (pintype "bidirectional"))
      (node (ref "XP2") (pin "2") (pinfunction "2_2") (pintype "passive"))
    )
    (net (code "77") (name "/PE2") (class "Default")
      (node (ref "DD1") (pin "1") (pinfunction "PE2_1") (pintype "bidirectional"))
      (node (ref "XP2") (pin "3") (pinfunction "3_3") (pintype "passive"))
    )
    (net (code "78") (name "/PE3") (class "Default")
      (node (ref "DD1") (pin "2") (pinfunction "PE3_2") (pintype "bidirectional"))
      (node (ref "XP2") (pin "4") (pinfunction "4_4") (pintype "passive"))
    )
    (net (code "79") (name "/PE4") (class "Default")
      (node (ref "DD1") (pin "3") (pinfunction "PE4_3") (pintype "bidirectional"))
      (node (ref "XP2") (pin "5") (pinfunction "5_5") (pintype "passive"))
    )
    (net (code "80") (name "/PE5") (class "Default")
      (node (ref "DD1") (pin "4") (pinfunction "PE5_4") (pintype "bidirectional"))
      (node (ref "XP2") (pin "6") (pinfunction "6_6") (pintype "passive"))
    )
    (net (code "81") (name "/PE6") (class "Default")
      (node (ref "DD1") (pin "5") (pinfunction "PE6_5") (pintype "bidirectional"))
      (node (ref "XP2") (pin "7") (pinfunction "7_7") (pintype "passive"))
    )
    (net (code "82") (name "/PE7") (class "Default")
      (node (ref "DD1") (pin "38") (pinfunction "PE7_38") (pintype "bidirectional"))
      (node (ref "XP2") (pin "8") (pinfunction "8_8") (pintype "passive"))
    )
    (net (code "83") (name "/PE8") (class "Default")
      (node (ref "DD1") (pin "39") (pinfunction "PE8_39") (pintype "bidirectional"))
      (node (ref "XP2") (pin "9") (pinfunction "9_9") (pintype "passive"))
    )
    (net (code "84") (name "/PE9") (class "Default")
      (node (ref "DD1") (pin "40") (pinfunction "PE9_40") (pintype "bidirectional"))
      (node (ref "XP2") (pin "10") (pinfunction "10_10") (pintype "passive"))
    )
    (net (code "85") (name "/PE10") (class "Default")
      (node (ref "DD1") (pin "41") (pinfunction "PE10_41") (pintype "bidirectional"))
      (node (ref "XP2") (pin "11") (pinfunction "11_11") (pintype "passive"))
    )
    (net (code "86") (name "/PE11") (class "Default")
      (node (ref "DD1") (pin "42") (pinfunction "PE11_42") (pintype "bidirectional"))
      (node (ref "XP2") (pin "12") (pinfunction "12_12") (pintype "passive"))
    )
    (net (code "87") (name "/PE12") (class "Default")
      (node (ref "DD1") (pin "43") (pinfunction "PE12_43") (pintype "bidirectional"))
      (node (ref "XP2") (pin "13") (pinfunction "13_13") (pintype "passive"))
    )
    (net (code "88") (name "/PE13") (class "Default")
      (node (ref "DD1") (pin "44") (pinfunction "PE13_44") (pintype "bidirectional"))
      (node (ref "XP2") (pin "14") (pinfunction "14_14") (pintype "passive"))
    )
    (net (code "89") (name "/PE14") (class "Default")
      (node (ref "DD1") (pin "45") (pinfunction "PE14_45") (pintype "bidirectional"))
      (node (ref "XP2") (pin "15") (pinfunction "15_15") (pintype "passive"))
    )
    (net (code "90") (name "/PE15") (class "Default")
      (node (ref "DD1") (pin "46") (pinfunction "PE15_46") (pintype "bidirectional"))
      (node (ref "XP2") (pin "16") (pinfunction "16_16") (pintype "passive"))
    )
    (net (code "91") (name "/RX_DV") (class "Default")
      (node (ref "X6") (pin "3") (pinfunction "3_3") (pintype "passive"))
    )
    (net (code "92") (name "/SD_CS") (class "Default")
      (node (ref "R29") (pin "1") (pinfunction "1_1") (pintype "passive"))
      (node (ref "R35") (pin "2") (pinfunction "2_2") (pintype "passive"))
      (node (ref "XS2") (pin "1") (pinfunction "1_1") (pintype "passive"))
      (node (ref "XS3") (pin "2") (pinfunction "2_2") (pintype "passive"))
    )
    (net (code "93") (name "/SD_MISO") (class "Default")
      (node (ref "R32") (pin "1") (pinfunction "1_1") (pintype "passive"))
      (node (ref "XS2") (pin "7") (pinfunction "7_7") (pintype "passive"))
      (node (ref "XS3") (pin "7") (pinfunction "7_7") (pintype "passive"))
    )
    (net (code "94") (name "/SD_MOSI") (class "Default")
      (node (ref "R30") (pin "1") (pinfunction "1_1") (pintype "passive"))
      (node (ref "XS2") (pin "2") (pinfunction "2_2") (pintype "passive"))
      (node (ref "XS3") (pin "3") (pinfunction "3_3") (pintype "passive"))
    )
    (net (code "95") (name "/SD_SCK") (class "Default")
      (node (ref "R31") (pin "1") (pinfunction "1_1") (pintype "passive"))
      (node (ref "XS2") (pin "5") (pinfunction "5_5") (pintype "passive"))
      (node (ref "XS3") (pin "5") (pinfunction "5_5") (pintype "passive"))
    )
    (net (code "96") (name "/SPI2_SCK") (class "Default")
      (node (ref "R15") (pin "1") (pinfunction "1_1") (pintype "passive"))
      (node (ref "X8") (pin "3") (pinfunction "3_3") (pintype "passive"))
      (node (ref "XP4") (pin "9") (pinfunction "9_9") (pintype "passive"))
    )
    (net (code "97") (name "/VBAT") (class "Default")
      (node (ref "DD1") (pin "6") (pinfunction "VBAT_6") (pintype "power_in"))
      (node (ref "X10") (pin "2") (pinfunction "2_2") (pintype "passive"))
    )
    (net (code "98") (name "/VDD_SD") (class "Default")
      (node (ref "C23") (pin "1") (pinfunction "+_1") (pintype "passive"))
      (node (ref "C24") (pin "1") (pinfunction "1_1") (pintype "passive"))
      (node (ref "L4") (pin "2") (pinfunction "2_2") (pintype "passive"))
      (node (ref "XS2") (pin "4") (pinfunction "4_4") (pintype "passive"))
      (node (ref "XS3") (pin "4") (pinfunction "4_4") (pintype "passive"))
    )
    (net (code "99") (name "5V") (class "Default")
      (node (ref "C5") (pin "1") (pinfunction "+_1") (pintype "passive"))
      (node (ref "C7") (pin "1") (pinfunction "1_1") (pintype "passive"))
      (node (ref "DA1") (pin "2") (pinfunction "Vout_2") (pintype "power_in"))
      (node (ref "DA1") (pin "4") (pinfunction "Vout_4") (pintype "passive"))
      (node (ref "X4") (pin "2") (pinfunction "2_2") (pintype "passive"))
    )
    (net (code "100") (name "AGND") (class "Default")
      (node (ref "VD1") (pin "1") (pinfunction "+_1") (pintype "passive"))
      (node (ref "X5") (pin "1") (pinfunction "1_1") (pintype "passive"))
    )
    (net (code "101") (name "GND") (class "Default")
      (node (ref "C1") (pin "2") (pinfunction "2_2") (pintype "passive"))
      (node (ref "C10") (pin "1") (pinfunction "1_1") (pintype "passive"))
      (node (ref "C11") (pin "1") (pinfunction "1_1") (pintype "passive"))
      (node (ref "C12") (pin "2") (pinfunction "-_2") (pintype "passive"))
      (node (ref "C13") (pin "2") (pinfunction "2_2") (pintype "passive"))
      (node (ref "C14") (pin "1") (pinfunction "1_1") (pintype "passive"))
      (node (ref "C15") (pin "2") (pinfunction "2_2") (pintype "passive"))
      (node (ref "C16") (pin "2") (pinfunction "2_2") (pintype "passive"))
      (node (ref "C17") (pin "2") (pinfunction "2_2") (pintype "passive"))
      (node (ref "C18") (pin "2") (pinfunction "2_2") (pintype "passive"))
      (node (ref "C19") (pin "2") (pinfunction "2_2") (pintype "passive"))
      (node (ref "C2") (pin "2") (pinfunction "2_2") (pintype "passive"))
      (node (ref "C20") (pin "2") (pinfunction "2_2") (pintype "passive"))
      (node (ref "C21") (pin "2") (pinfunction "2_2") (pintype "passive"))
      (node (ref "C22") (pin "2") (pinfunction "2_2") (pintype "passive"))
      (node (ref "C23") (pin "2") (pinfunction "-_2") (pintype "passive"))
      (node (ref "C24") (pin "2") (pinfunction "2_2") (pintype "passive"))
      (node (ref "C3") (pin "2") (pinfunction "-_2") (pintype "passive"))
      (node (ref "C4") (pin "2") (pinfunction "-_2") (pintype "passive"))
      (node (ref "C5") (pin "2") (pinfunction "-_2") (pintype "passive"))
      (node (ref "C6") (pin "2") (pinfunction "-_2") (pintype "passive"))
      (node (ref "C7") (pin "2") (pinfunction "2_2") (pintype "passive"))
      (node (ref "C8") (pin "2") (pinfunction "2_2") (pintype "passive"))
      (node (ref "C9") (pin "1") (pinfunction "1_1") (pintype "passive"))
      (node (ref "DA1") (pin "1") (pinfunction "ADJ/GND_1") (pintype "power_in"))
      (node (ref "DA2") (pin "1") (pinfunction "ADJ/GND_1") (pintype "power_in"))
      (node (ref "DD1") (pin "10") (pinfunction "VSS_5_10") (pintype "power_in"))
      (node (ref "DD1") (pin "19") (pinfunction "VSSA_19") (pintype "power_in"))
      (node (ref "DD1") (pin "20") (pinfunction "VREF-_20") (pintype "power_in"))
      (node (ref "DD1") (pin "27") (pinfunction "VSS_4_27") (pintype "power_in"))
      (node (ref "DD1") (pin "49") (pinfunction "VSS_1_49") (pintype "power_in"))
      (node (ref "DD1") (pin "74") (pinfunction "VSS_2_74") (pintype "power_in"))
      (node (ref "DD1") (pin "99") (pinfunction "VSS_3_99") (pintype "power_in"))
      (node (ref "DD2") (pin "2") (pinfunction "GND_2") (pintype "power_in"))
      (node (ref "DD3") (pin "2") (pinfunction "GND_2") (pintype "power_in"))
      (node (ref "E1") (pin "2") (pinfunction "2_2") (pintype "passive"))
      (node (ref "R2") (pin "1") (pinfunction "1_1") (pintype "passive"))
      (node (ref "R37") (pin "2") (pinfunction "2_2") (pintype "passive"))
      (node (ref "R39") (pin "2") (pinfunction "2_2") (pintype "passive"))
      (node (ref "R4") (pin "1") (pinfunction "1_1") (pintype "passive"))
      (node (ref "R6") (pin "1") (pinfunction "1_1") (pintype "passive"))
      (node (ref "SB1") (pin "1") (pinfunction "1_1") (pintype "passive"))
      (node (ref "SB1") (pin "2") (pinfunction "2_2") (pintype "passive"))
      (node (ref "X13") (pin "1") (pinfunction "1_1") (pintype "passive"))
      (node (ref "X14") (pin "1") (pinfunction "1_1") (pintype "passive"))
      (node (ref "X5") (pin "2") (pinfunction "2_2") (pintype "passive"))
      (node (ref "X7") (pin "3") (pinfunction "3_3") (pintype "passive"))
      (node (ref "X9") (pin "3") (pinfunction "3_3") (pintype "passive"))
      (node (ref "XP1") (pin "10") (pinfunction "10_10") (pintype "passive"))
      (node (ref "XP1") (pin "12") (pinfunction "12_12") (pintype "passive"))
      (node (ref "XP1") (pin "14") (pinfunction "14_14") (pintype "passive"))
      (node (ref "XP1") (pin "16") (pinfunction "16_16") (pintype "passive"))
      (node (ref "XP1") (pin "18") (pinfunction "18_18") (pintype "passive"))
      (node (ref "XP1") (pin "20") (pinfunction "20_20") (pintype "passive"))
      (node (ref "XP1") (pin "4") (pinfunction "4_4") (pintype "passive"))
      (node (ref "XP1") (pin "6") (pinfunction "6_6") (pintype "passive"))
      (node (ref "XP1") (pin "8") (pinfunction "8_8") (pintype "passive"))
      (node (ref "XP2") (pin "18") (pinfunction "18_18") (pintype "passive"))
      (node (ref "XP2") (pin "20") (pinfunction "20_20") (pintype "passive"))
      (node (ref "XP3") (pin "2") (pinfunction "2_2") (pintype "passive"))
      (node (ref "XP4") (pin "2") (pinfunction "2_2") (pintype "passive"))
      (node (ref "XP5") (pin "2") (pinfunction "2_2") (pintype "passive"))
      (node (ref "XP6") (pin "2") (pinfunction "2_2") (pintype "passive"))
      (node (ref "XS1") (pin "12") (pinfunction "12_12") (pintype "passive"))
      (node (ref "XS1") (pin "3") (pinfunction "3_3") (pintype "passive"))
      (node (ref "XS1") (pin "6") (pinfunction "6_6") (pintype "passive"))
      (node (ref "XS2") (pin "12") (pinfunction "12_12") (pintype "passive"))
      (node (ref "XS2") (pin "3") (pinfunction "3_3") (pintype "passive"))
      (node (ref "XS2") (pin "6") (pinfunction "6_6") (pintype "passive"))
      (node (ref "XS3") (pin "10") (pinfunction "10_10") (pintype "passive"))
      (node (ref "XS3") (pin "6") (pinfunction "6_6") (pintype "passive"))
      (node (ref "XT1") (pin "2") (pintype "passive"))
      (node (ref "XT2") (pin "2") (pintype "passive"))
      (node (ref "XT3") (pin "2") (pinfunction "2_2") (pintype "passive"))
      (node (ref "XT4") (pin "2") (pinfunction "2_2") (pintype "passive"))
    )
    (net (code "102") (name "Net-(C10-Pad2)") (class "Default")
      (node (ref "C10") (pin "2") (pinfunction "2_2") (pintype "passive"))
      (node (ref "R9") (pin "1") (pinfunction "1_1") (pintype "passive"))
      (node (ref "ZQ1") (pin "1") (pinfunction "1_1") (pintype "passive"))
    )
    (net (code "103") (name "Net-(C12-+)") (class "Default")
      (node (ref "C12") (pin "1") (pinfunction "+_1") (pintype "passive"))
      (node (ref "C13") (pin "1") (pinfunction "1_1") (pintype "passive"))
      (node (ref "DD1") (pin "22") (pinfunction "VDDA_22") (pintype "power_in"))
      (node (ref "L3") (pin "2") (pinfunction "2_2") (pintype "passive"))
    )
    (net (code "104") (name "Net-(DD1-VREF+)") (class "Default")
      (node (ref "C14") (pin "2") (pinfunction "2_2") (pintype "passive"))
      (node (ref "DD1") (pin "21") (pinfunction "VREF+_21") (pintype "power_in"))
      (node (ref "R13") (pin "1") (pinfunction "1_1") (pintype "passive"))
    )
    (net (code "105") (name "Net-(DD2-CANH)") (class "Default")
      (node (ref "DD2") (pin "7") (pinfunction "CANH_7") (pintype "passive"))
      (node (ref "X15") (pin "1") (pinfunction "1_1") (pintype "passive"))
      (node (ref "XT3") (pin "1") (pinfunction "1_1") (pintype "passive"))
    )
    (net (code "106") (name "Net-(DD2-CANL)") (class "Default")
      (node (ref "DD2") (pin "6") (pinfunction "CANL_6") (pintype "passive"))
      (node (ref "R38") (pin "1") (pinfunction "1_1") (pintype "passive"))
      (node (ref "XT3") (pin "3") (pinfunction "3_3") (pintype "passive"))
    )
    (net (code "107") (name "Net-(DD2-Rs)") (class "Default")
      (node (ref "DD2") (pin "8") (pinfunction "Rs_8") (pintype "passive"))
      (node (ref "R37") (pin "1") (pinfunction "1_1") (pintype "passive"))
      (node (ref "X13") (pin "2") (pinfunction "2_2") (pintype "passive"))
    )
    (net (code "108") (name "Net-(DD3-CANH)") (class "Default")
      (node (ref "DD3") (pin "7") (pinfunction "CANH_7") (pintype "passive"))
      (node (ref "X16") (pin "1") (pinfunction "1_1") (pintype "passive"))
      (node (ref "XT4") (pin "1") (pinfunction "1_1") (pintype "passive"))
    )
    (net (code "109") (name "Net-(DD3-CANL)") (class "Default")
      (node (ref "DD3") (pin "6") (pinfunction "CANL_6") (pintype "passive"))
      (node (ref "R40") (pin "1") (pinfunction "1_1") (pintype "passive"))
      (node (ref "XT4") (pin "3") (pinfunction "3_3") (pintype "passive"))
    )
    (net (code "110") (name "Net-(DD3-Rs)") (class "Default")
      (node (ref "DD3") (pin "8") (pinfunction "Rs_8") (pintype "passive"))
      (node (ref "R39") (pin "1") (pinfunction "1_1") (pintype "passive"))
      (node (ref "X14") (pin "2") (pinfunction "2_2") (pintype "passive"))
    )
    (net (code "111") (name "Net-(E1-Pad1)") (class "Default")
      (node (ref "E1") (pin "1") (pinfunction "1_1") (pintype "passive"))
      (node (ref "X10") (pin "3") (pinfunction "3_3") (pintype "passive"))
    )
    (net (code "112") (name "Net-(L1-Pad1)") (class "Default")
      (node (ref "L1") (pin "1") (pinfunction "1_1") (pintype "passive"))
      (node (ref "XP3") (pin "1") (pinfunction "1_1") (pintype "passive"))
    )
    (net (code "113") (name "Net-(L2-Pad1)") (class "Default")
      (node (ref "L2") (pin "1") (pinfunction "1_1") (pintype "passive"))
      (node (ref "XP3") (pin "3") (pinfunction "3_3") (pintype "passive"))
    )
    (net (code "114") (name "Net-(R2-Pad2)") (class "Default")
      (node (ref "R2") (pin "2") (pinfunction "2_2") (pintype "passive"))
      (node (ref "XP1") (pin "19") (pinfunction "19_19") (pintype "passive"))
    )
    (net (code "115") (name "Net-(R4-Pad2)") (class "Default")
      (node (ref "R4") (pin "2") (pinfunction "2_2") (pintype "passive"))
      (node (ref "XP1") (pin "17") (pinfunction "17_17") (pintype "passive"))
    )
    (net (code "116") (name "Net-(R10-Pad1)") (class "Default")
      (node (ref "R10") (pin "1") (pinfunction "1_1") (pintype "passive"))
      (node (ref "X7") (pin "2") (pinfunction "2_2") (pintype "passive"))
    )
    (net (code "117") (name "Net-(R11-Pad1)") (class "Default")
      (node (ref "R11") (pin "1") (pinfunction "1_1") (pintype "passive"))
      (node (ref "X9") (pin "2") (pinfunction "2_2") (pintype "passive"))
    )
    (net (code "118") (name "Net-(R19-Pad1)") (class "Default")
      (node (ref "R19") (pin "1") (pinfunction "1_1") (pintype "passive"))
      (node (ref "XS1") (pin "5") (pinfunction "5_5") (pintype "passive"))
    )
    (net (code "119") (name "Net-(R20-Pad1)") (class "Default")
      (node (ref "R20") (pin "1") (pinfunction "1_1") (pintype "passive"))
      (node (ref "XS1") (pin "8") (pinfunction "8_8") (pintype "passive"))
    )
    (net (code "120") (name "Net-(R21-Pad1)") (class "Default")
      (node (ref "R21") (pin "1") (pinfunction "1_1") (pintype "passive"))
      (node (ref "XS1") (pin "1") (pinfunction "1_1") (pintype "passive"))
    )
    (net (code "121") (name "Net-(R22-Pad1)") (class "Default")
      (node (ref "R22") (pin "1") (pinfunction "1_1") (pintype "passive"))
      (node (ref "XS1") (pin "2") (pinfunction "2_2") (pintype "passive"))
    )
    (net (code "122") (name "Net-(R23-Pad1)") (class "Default")
      (node (ref "R23") (pin "1") (pinfunction "1_1") (pintype "passive"))
      (node (ref "XS1") (pin "7") (pinfunction "7_7") (pintype "passive"))
    )
    (net (code "123") (name "Net-(R24-Pad1)") (class "Default")
      (node (ref "R24") (pin "1") (pinfunction "1_1") (pintype "passive"))
      (node (ref "XS1") (pin "10") (pinfunction "10_10") (pintype "passive"))
    )
    (net (code "124") (name "Net-(R25-Pad1)") (class "Default")
      (node (ref "R25") (pin "1") (pinfunction "1_1") (pintype "passive"))
      (node (ref "XS1") (pin "11") (pinfunction "11_11") (pintype "passive"))
    )
    (net (code "125") (name "Net-(R26-Pad2)") (class "Default")
      (node (ref "R26") (pin "2") (pinfunction "2_2") (pintype "passive"))
      (node (ref "XS1") (pin "9") (pinfunction "9_9") (pintype "passive"))
    )
    (net (code "126") (name "Net-(R33-Pad2)") (class "Default")
      (node (ref "R33") (pin "2") (pinfunction "2_2") (pintype "passive"))
      (node (ref "X13") (pin "3") (pinfunction "3_3") (pintype "passive"))
    )
    (net (code "127") (name "Net-(R34-Pad2)") (class "Default")
      (node (ref "R34") (pin "2") (pinfunction "2_2") (pintype "passive"))
      (node (ref "X14") (pin "3") (pinfunction "3_3") (pintype "passive"))
    )
    (net (code "128") (name "Net-(R36-Pad1)") (class "Default")
      (node (ref "R36") (pin "1") (pinfunction "1_1") (pintype "passive"))
      (node (ref "XS2") (pin "8") (pinfunction "8_8") (pintype "passive"))
    )
    (net (code "129") (name "Net-(R38-Pad2)") (class "Default")
      (node (ref "R38") (pin "2") (pinfunction "2_2") (pintype "passive"))
      (node (ref "X15") (pin "2") (pinfunction "2_2") (pintype "passive"))
    )
    (net (code "130") (name "Net-(R40-Pad2)") (class "Default")
      (node (ref "R40") (pin "2") (pinfunction "2_2") (pintype "passive"))
      (node (ref "X16") (pin "2") (pinfunction "2_2") (pintype "passive"))
    )
    (net (code "131") (name "Net-(R41-Pad1)") (class "Default")
      (node (ref "R41") (pin "1") (pinfunction "1_1") (pintype "passive"))
      (node (ref "XS2") (pin "9") (pinfunction "9_9") (pintype "passive"))
    )
    (net (code "132") (name "Net-(X1-Pad2)") (class "Default")
      (node (ref "X1") (pin "2") (pinfunction "2_2") (pintype "passive"))
      (node (ref "XP2") (pin "17") (pinfunction "17_17") (pintype "passive"))
    )
    (net (code "133") (name "Net-(X2-Pad2)") (class "Default")
      (node (ref "X2") (pin "2") (pinfunction "2_2") (pintype "passive"))
      (node (ref "XP2") (pin "19") (pinfunction "19_19") (pintype "passive"))
    )
    (net (code "134") (name "Net-(X11-Pad2)") (class "Default")
      (node (ref "X11") (pin "2") (pinfunction "2_2") (pintype "passive"))
      (node (ref "XS2") (pin "10") (pinfunction "10_10") (pintype "passive"))
      (node (ref "XS3") (pin "9") (pinfunction "9_9") (pintype "passive"))
    )
    (net (code "135") (name "Net-(X12-Pad2)") (class "Default")
      (node (ref "X12") (pin "2") (pinfunction "2_2") (pintype "passive"))
      (node (ref "XS2") (pin "11") (pinfunction "11_11") (pintype "passive"))
    )
    (net (code "136") (name "unconnected-(DD1-NC-Pad73)") (class "Default")
      (node (ref "DD1") (pin "73") (pinfunction "NC_73") (pintype "passive"))
    )
    (net (code "137") (name "unconnected-(DD2-Vref-Pad5)") (class "Default")
      (node (ref "DD2") (pin "5") (pinfunction "Vref_5") (pintype "passive"))
    )
    (net (code "138") (name "unconnected-(DD3-Vref-Pad5)") (class "Default")
      (node (ref "DD3") (pin "5") (pinfunction "Vref_5") (pintype "passive"))
    )
    (net (code "139") (name "unconnected-(XP1-Pad11)") (class "Default")
      (node (ref "XP1") (pin "11") (pinfunction "11_11") (pintype "passive"))
    )
    (net (code "140") (name "unconnected-(XP3-Pad4)") (class "Default")
      (node (ref "XP3") (pin "4") (pinfunction "4_4") (pintype "passive"))
    )
    (net (code "141") (name "unconnected-(XP3-Pad5)") (class "Default")
      (node (ref "XP3") (pin "5") (pinfunction "5_5") (pintype "passive"))
    )
    (net (code "142") (name "unconnected-(XP3-Pad6)") (class "Default")
      (node (ref "XP3") (pin "6") (pinfunction "6_6") (pintype "passive"))
    )
    (net (code "143") (name "unconnected-(XP6-Pad3)") (class "Default")
      (node (ref "XP6") (pin "3") (pinfunction "3_3") (pintype "passive"))
    )
    (net (code "144") (name "unconnected-(XP6-Pad4)") (class "Default")
      (node (ref "XP6") (pin "4") (pinfunction "4_4") (pintype "passive"))
    )
    (net (code "145") (name "unconnected-(XS3-Pad1)") (class "Default")
      (node (ref "XS3") (pin "1") (pinfunction "1_1") (pintype "passive"))
    )
    (net (code "146") (name "unconnected-(XS3-Pad8)") (class "Default")
      (node (ref "XS3") (pin "8") (pinfunction "8_8") (pintype "passive"))
    )
  )
)
